# ContunityTestingRig.net
KiCad netlist of a schematic drawn in EAGLE
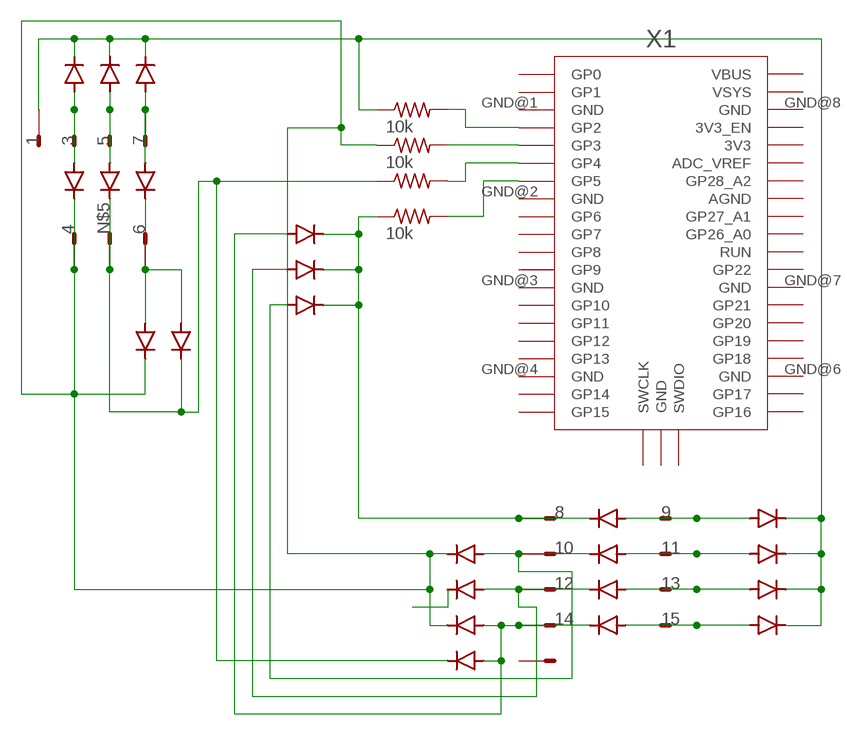
[diagram p0: schematic, sheet 1]

(export (version "E")
  (design (tool "Eeschema 10.0.6"))
  (components
    (comp (ref "D1")
      (value "SCHOTTKY")
      (footprint "eagle-import:MINI-SMA")
      (libsource (lib "eagle-import") (part "DIODE_SCHOTTKY_CDBM1100-G"))
    )
    (comp (ref "D2")
      (value "SCHOTTKY")
      (footprint "eagle-import:MINI-SMA")
      (libsource (lib "eagle-import") (part "DIODE_SCHOTTKY_CDBM1100-G"))
    )
    (comp (ref "D3")
      (value "SCHOTTKY")
      (footprint "eagle-import:MINI-SMA")
      (libsource (lib "eagle-import") (part "DIODE_SCHOTTKY_CDBM1100-G"))
    )
    (comp (ref "D4")
      (value "SCHOTTKY")
      (footprint "eagle-import:MINI-SMA")
      (libsource (lib "eagle-import") (part "DIODE_SCHOTTKY_CDBM1100-G"))
    )
    (comp (ref "D5")
      (value "SCHOTTKY")
      (footprint "eagle-import:MINI-SMA")
      (libsource (lib "eagle-import") (part "DIODE_SCHOTTKY_CDBM1100-G"))
    )
    (comp (ref "D6")
      (value "SCHOTTKY")
      (footprint "eagle-import:MINI-SMA")
      (libsource (lib "eagle-import") (part "DIODE_SCHOTTKY_CDBM1100-G"))
    )
    (comp (ref "D7")
      (value "SCHOTTKY")
      (footprint "eagle-import:MINI-SMA")
      (libsource (lib "eagle-import") (part "DIODE_SCHOTTKY_CDBM1100-G"))
    )
    (comp (ref "D8")
      (value "SCHOTTKY")
      (footprint "eagle-import:MINI-SMA")
      (libsource (lib "eagle-import") (part "DIODE_SCHOTTKY_CDBM1100-G"))
    )
    (comp (ref "D9")
      (value "SCHOTTKY")
      (footprint "eagle-import:MINI-SMA")
      (libsource (lib "eagle-import") (part "DIODE_SCHOTTKY_CDBM1100-G"))
    )
    (comp (ref "D10")
      (value "SCHOTTKY")
      (footprint "eagle-import:MINI-SMA")
      (libsource (lib "eagle-import") (part "DIODE_SCHOTTKY_CDBM1100-G"))
    )
    (comp (ref "D11")
      (value "SCHOTTKY")
      (footprint "eagle-import:MINI-SMA")
      (libsource (lib "eagle-import") (part "DIODE_SCHOTTKY_CDBM1100-G"))
    )
    (comp (ref "D12")
      (value "SCHOTTKY")
      (footprint "eagle-import:MINI-SMA")
      (libsource (lib "eagle-import") (part "DIODE_SCHOTTKY_CDBM1100-G"))
    )
    (comp (ref "D13")
      (value "SCHOTTKY")
      (footprint "eagle-import:MINI-SMA")
      (libsource (lib "eagle-import") (part "DIODE_SCHOTTKY_CDBM1100-G"))
    )
    (comp (ref "D14")
      (value "SCHOTTKY")
      (footprint "eagle-import:MINI-SMA")
      (libsource (lib "eagle-import") (part "DIODE_SCHOTTKY_CDBM1100-G"))
    )
    (comp (ref "D15")
      (value "SCHOTTKY")
      (footprint "eagle-import:MINI-SMA")
      (libsource (lib "eagle-import") (part "DIODE_SCHOTTKY_CDBM1100-G"))
    )
    (comp (ref "D16")
      (value "SCHOTTKY")
      (footprint "eagle-import:MINI-SMA")
      (libsource (lib "eagle-import") (part "DIODE_SCHOTTKY_CDBM1100-G"))
    )
    (comp (ref "D17")
      (value "SCHOTTKY")
      (footprint "eagle-import:MINI-SMA")
      (libsource (lib "eagle-import") (part "DIODE_SCHOTTKY_CDBM1100-G"))
    )
    (comp (ref "D18")
      (value "SCHOTTKY")
      (footprint "eagle-import:MINI-SMA")
      (libsource (lib "eagle-import") (part "DIODE_SCHOTTKY_CDBM1100-G"))
    )
    (comp (ref "D19")
      (value "SCHOTTKY")
      (footprint "eagle-import:MINI-SMA")
      (libsource (lib "eagle-import") (part "DIODE_SCHOTTKY_CDBM1100-G"))
    )
    (comp (ref "D20")
      (value "SCHOTTKY")
      (footprint "eagle-import:MINI-SMA")
      (libsource (lib "eagle-import") (part "DIODE_SCHOTTKY_CDBM1100-G"))
    )
    (comp (ref "D21")
      (value "SCHOTTKY")
      (footprint "eagle-import:MINI-SMA")
      (libsource (lib "eagle-import") (part "DIODE_SCHOTTKY_CDBM1100-G"))
    )
    (comp (ref "D22")
      (value "SCHOTTKY")
      (footprint "eagle-import:MINI-SMA")
      (libsource (lib "eagle-import") (part "DIODE_SCHOTTKY_CDBM1100-G"))
    )
    (comp (ref "D23")
      (value "SCHOTTKY")
      (footprint "eagle-import:MINI-SMA")
      (libsource (lib "eagle-import") (part "DIODE_SCHOTTKY_CDBM1100-G"))
    )
    (comp (ref "R1")
      (value "10k")
      (footprint "eagle-import:R1206FAB")
      (libsource (lib "eagle-import") (part "R1206FAB"))
    )
    (comp (ref "R2")
      (value "10k")
      (footprint "eagle-import:R1206FAB")
      (libsource (lib "eagle-import") (part "R1206FAB"))
    )
    (comp (ref "R3")
      (value "10k")
      (footprint "eagle-import:R1206FAB")
      (libsource (lib "eagle-import") (part "R1206FAB"))
    )
    (comp (ref "R4")
      (value "10k")
      (footprint "eagle-import:R1206FAB")
      (libsource (lib "eagle-import") (part "R1206FAB"))
    )
    (comp (ref "SV1")
      (value "16E")
      (footprint "eagle-import:16P")
      (libsource (lib "eagle-import") (part "16E"))
    )
    (comp (ref "X1")
      (value "RPI_PICO_IG-SMD")
      (footprint "eagle-import:RPI_PICO")
      (libsource (lib "eagle-import") (part "RPI_PICO_IG-SMD"))
    )
  )
  (nets
    (net (code "1") (name "/1") (class "Default")
      (node (ref "D1") (pin "KATHODE") (pinfunction "KATHODE_KATHODE") (pintype "bidirectional"))
      (node (ref "D13") (pin "KATHODE") (pinfunction "KATHODE_KATHODE") (pintype "bidirectional"))
      (node (ref "D14") (pin "KATHODE") (pinfunction "KATHODE_KATHODE") (pintype "bidirectional"))
      (node (ref "D15") (pin "KATHODE") (pinfunction "KATHODE_KATHODE") (pintype "bidirectional"))
      (node (ref "D16") (pin "KATHODE") (pinfunction "KATHODE_KATHODE") (pintype "bidirectional"))
      (node (ref "D2") (pin "KATHODE") (pinfunction "KATHODE_KATHODE") (pintype "bidirectional"))
      (node (ref "D3") (pin "KATHODE") (pinfunction "KATHODE_KATHODE") (pintype "bidirectional"))
      (node (ref "R1") (pin "1") (pinfunction "1_1") (pintype "passive"))
      (node (ref "SV1") (pin "1") (pinfunction "S_1") (pintype "passive"))
    )
    (net (code "2") (name "/3") (class "Default")
      (node (ref "D1") (pin "ANODE") (pinfunction "ANODE_ANODE") (pintype "bidirectional"))
      (node (ref "D4") (pin "ANODE") (pinfunction "ANODE_ANODE") (pintype "bidirectional"))
      (node (ref "SV1") (pin "3") (pinfunction "S_3") (pintype "passive"))
    )
    (net (code "3") (name "/4") (class "Default")
      (node (ref "D17") (pin "KATHODE") (pinfunction "KATHODE_KATHODE") (pintype "bidirectional"))
      (node (ref "D18") (pin "KATHODE") (pinfunction "KATHODE_KATHODE") (pintype "bidirectional"))
      (node (ref "D4") (pin "KATHODE") (pinfunction "KATHODE_KATHODE") (pintype "bidirectional"))
      (node (ref "D7") (pin "KATHODE") (pinfunction "KATHODE_KATHODE") (pintype "bidirectional"))
      (node (ref "R2") (pin "1") (pinfunction "1_1") (pintype "passive"))
      (node (ref "SV1") (pin "2") (pinfunction "S_2") (pintype "passive"))
    )
    (net (code "4") (name "/5") (class "Default")
      (node (ref "D2") (pin "ANODE") (pinfunction "ANODE_ANODE") (pintype "bidirectional"))
      (node (ref "D5") (pin "ANODE") (pinfunction "ANODE_ANODE") (pintype "bidirectional"))
      (node (ref "SV1") (pin "5") (pinfunction "S_5") (pintype "passive"))
    )
    (net (code "5") (name "/6") (class "Default")
      (node (ref "D6") (pin "KATHODE") (pinfunction "KATHODE_KATHODE") (pintype "bidirectional"))
      (node (ref "D7") (pin "ANODE") (pinfunction "ANODE_ANODE") (pintype "bidirectional"))
      (node (ref "D8") (pin "ANODE") (pinfunction "ANODE_ANODE") (pintype "bidirectional"))
      (node (ref "SV1") (pin "6") (pinfunction "S_6") (pintype "passive"))
    )
    (net (code "6") (name "/7") (class "Default")
      (node (ref "D3") (pin "ANODE") (pinfunction "ANODE_ANODE") (pintype "bidirectional"))
      (node (ref "D6") (pin "ANODE") (pinfunction "ANODE_ANODE") (pintype "bidirectional"))
      (node (ref "SV1") (pin "7") (pinfunction "S_7") (pintype "passive"))
    )
    (net (code "7") (name "/8") (class "Default")
      (node (ref "D21") (pin "KATHODE") (pinfunction "KATHODE_KATHODE") (pintype "bidirectional"))
      (node (ref "D22") (pin "KATHODE") (pinfunction "KATHODE_KATHODE") (pintype "bidirectional"))
      (node (ref "D23") (pin "KATHODE") (pinfunction "KATHODE_KATHODE") (pintype "bidirectional"))
      (node (ref "D9") (pin "KATHODE") (pinfunction "KATHODE_KATHODE") (pintype "bidirectional"))
      (node (ref "R4") (pin "1") (pinfunction "1_1") (pintype "passive"))
      (node (ref "SV1") (pin "8") (pinfunction "S_8") (pintype "passive"))
    )
    (net (code "8") (name "/9") (class "Default")
      (node (ref "D13") (pin "ANODE") (pinfunction "ANODE_ANODE") (pintype "bidirectional"))
      (node (ref "D9") (pin "ANODE") (pinfunction "ANODE_ANODE") (pintype "bidirectional"))
      (node (ref "SV1") (pin "9") (pinfunction "S_9") (pintype "passive"))
    )
    (net (code "9") (name "/10") (class "Default")
      (node (ref "D10") (pin "KATHODE") (pinfunction "KATHODE_KATHODE") (pintype "bidirectional"))
      (node (ref "D17") (pin "ANODE") (pinfunction "ANODE_ANODE") (pintype "bidirectional"))
      (node (ref "D23") (pin "ANODE") (pinfunction "ANODE_ANODE") (pintype "bidirectional"))
      (node (ref "SV1") (pin "10") (pinfunction "S_10") (pintype "passive"))
    )
    (net (code "10") (name "/11") (class "Default")
      (node (ref "D10") (pin "ANODE") (pinfunction "ANODE_ANODE") (pintype "bidirectional"))
      (node (ref "D14") (pin "ANODE") (pinfunction "ANODE_ANODE") (pintype "bidirectional"))
      (node (ref "SV1") (pin "11") (pinfunction "S_11") (pintype "passive"))
    )
    (net (code "11") (name "/12") (class "Default")
      (node (ref "D11") (pin "KATHODE") (pinfunction "KATHODE_KATHODE") (pintype "bidirectional"))
      (node (ref "D19") (pin "ANODE") (pinfunction "ANODE_ANODE") (pintype "bidirectional"))
      (node (ref "D22") (pin "ANODE") (pinfunction "ANODE_ANODE") (pintype "bidirectional"))
      (node (ref "SV1") (pin "12") (pinfunction "S_12") (pintype "passive"))
    )
    (net (code "12") (name "/13") (class "Default")
      (node (ref "D11") (pin "ANODE") (pinfunction "ANODE_ANODE") (pintype "bidirectional"))
      (node (ref "D15") (pin "ANODE") (pinfunction "ANODE_ANODE") (pintype "bidirectional"))
      (node (ref "SV1") (pin "13") (pinfunction "S_13") (pintype "passive"))
    )
    (net (code "13") (name "/14") (class "Default")
      (node (ref "D12") (pin "KATHODE") (pinfunction "KATHODE_KATHODE") (pintype "bidirectional"))
      (node (ref "D18") (pin "ANODE") (pinfunction "ANODE_ANODE") (pintype "bidirectional"))
      (node (ref "D20") (pin "ANODE") (pinfunction "ANODE_ANODE") (pintype "bidirectional"))
      (node (ref "D21") (pin "ANODE") (pinfunction "ANODE_ANODE") (pintype "bidirectional"))
      (node (ref "SV1") (pin "14") (pinfunction "S_14") (pintype "passive"))
    )
    (net (code "14") (name "/15") (class "Default")
      (node (ref "D12") (pin "ANODE") (pinfunction "ANODE_ANODE") (pintype "bidirectional"))
      (node (ref "D16") (pin "ANODE") (pinfunction "ANODE_ANODE") (pintype "bidirectional"))
      (node (ref "SV1") (pin "15") (pinfunction "S_15") (pintype "passive"))
    )
    (net (code "15") (name "/N$5") (class "Default")
      (node (ref "D20") (pin "KATHODE") (pinfunction "KATHODE_KATHODE") (pintype "bidirectional"))
      (node (ref "D5") (pin "KATHODE") (pinfunction "KATHODE_KATHODE") (pintype "bidirectional"))
      (node (ref "D8") (pin "KATHODE") (pinfunction "KATHODE_KATHODE") (pintype "bidirectional"))
      (node (ref "R3") (pin "1") (pinfunction "1_1") (pintype "passive"))
      (node (ref "SV1") (pin "4") (pinfunction "S_4") (pintype "passive"))
    )
    (net (code "16") (name "Net-(R1-Pad2)") (class "Default")
      (node (ref "R1") (pin "2") (pinfunction "2_2") (pintype "passive"))
      (node (ref "X1") (pin "GP2") (pinfunction "GP2_GP2") (pintype "bidirectional"))
    )
    (net (code "17") (name "Net-(R2-Pad2)") (class "Default")
      (node (ref "R2") (pin "2") (pinfunction "2_2") (pintype "passive"))
      (node (ref "X1") (pin "GP3") (pinfunction "GP3_GP3") (pintype "bidirectional"))
    )
    (net (code "18") (name "Net-(R3-Pad2)") (class "Default")
      (node (ref "R3") (pin "2") (pinfunction "2_2") (pintype "passive"))
      (node (ref "X1") (pin "GP4") (pinfunction "GP4_GP4") (pintype "bidirectional"))
    )
    (net (code "19") (name "Net-(R4-Pad2)") (class "Default")
      (node (ref "R4") (pin "2") (pinfunction "2_2") (pintype "passive"))
      (node (ref "X1") (pin "GP5") (pinfunction "GP5_GP5") (pintype "bidirectional"))
    )
    (net (code "20") (name "unconnected-(D19-PadKATHODE)") (class "Default")
      (node (ref "D19") (pin "KATHODE") (pinfunction "KATHODE_KATHODE") (pintype "bidirectional"))
    )
    (net (code "21") (name "unconnected-(SV1H-S-Pad16)") (class "Default")
      (node (ref "SV1") (pin "16") (pinfunction "S_16") (pintype "passive"))
    )
    (net (code "22") (name "unconnected-(X1-GND-PadGND@1)") (class "Default")
      (node (ref "X1") (pin "GND@1") (pinfunction "GND_GND@1") (pintype "bidirectional"))
    )
    (net (code "23") (name "unconnected-(X1-GND-PadGND@2)") (class "Default")
      (node (ref "X1") (pin "GND@2") (pinfunction "GND_GND@2") (pintype "bidirectional"))
    )
    (net (code "24") (name "unconnected-(X1-GND-PadGND@3)") (class "Default")
      (node (ref "X1") (pin "GND@3") (pinfunction "GND_GND@3") (pintype "bidirectional"))
    )
    (net (code "25") (name "unconnected-(X1-GND-PadGND@4)") (class "Default")
      (node (ref "X1") (pin "GND@4") (pinfunction "GND_GND@4") (pintype "bidirectional"))
    )
    (net (code "26") (name "unconnected-(X1-GND-PadGND@5)") (class "Default")
      (node (ref "X1") (pin "GND@5") (pinfunction "GND_GND@5") (pintype "bidirectional"))
    )
    (net (code "27") (name "unconnected-(X1-GND-PadGND@6)") (class "Default")
      (node (ref "X1") (pin "GND@6") (pinfunction "GND_GND@6") (pintype "bidirectional"))
    )
    (net (code "28") (name "unconnected-(X1-GND-PadGND@7)") (class "Default")
      (node (ref "X1") (pin "GND@7") (pinfunction "GND_GND@7") (pintype "bidirectional"))
    )
    (net (code "29") (name "unconnected-(X1-GND-PadGND@8)") (class "Default")
      (node (ref "X1") (pin "GND@8") (pinfunction "GND_GND@8") (pintype "bidirectional"))
    )
    (net (code "30") (name "unconnected-(X1-Pad3V3)") (class "Default")
      (node (ref "X1") (pin "3V3") (pinfunction "3V3_3V3") (pintype "bidirectional"))
    )
    (net (code "31") (name "unconnected-(X1-Pad3V3_EN)") (class "Default")
      (node (ref "X1") (pin "3V3_EN") (pinfunction "3V3_EN_3V3_EN") (pintype "bidirectional"))
    )
    (net (code "32") (name "unconnected-(X1-PadADC_VREF)") (class "Default")
      (node (ref "X1") (pin "ADC_VREF") (pinfunction "ADC_VREF_ADC_VREF") (pintype "bidirectional"))
    )
    (net (code "33") (name "unconnected-(X1-PadAGND)") (class "Default")
      (node (ref "X1") (pin "AGND") (pinfunction "AGND_AGND") (pintype "bidirectional"))
    )
    (net (code "34") (name "unconnected-(X1-PadGP0)") (class "Default")
      (node (ref "X1") (pin "GP0") (pinfunction "GP0_GP0") (pintype "bidirectional"))
    )
    (net (code "35") (name "unconnected-(X1-PadGP1)") (class "Default")
      (node (ref "X1") (pin "GP1") (pinfunction "GP1_GP1") (pintype "bidirectional"))
    )
    (net (code "36") (name "unconnected-(X1-PadGP6)") (class "Default")
      (node (ref "X1") (pin "GP6") (pinfunction "GP6_GP6") (pintype "bidirectional"))
    )
    (net (code "37") (name "unconnected-(X1-PadGP7)") (class "Default")
      (node (ref "X1") (pin "GP7") (pinfunction "GP7_GP7") (pintype "bidirectional"))
    )
    (net (code "38") (name "unconnected-(X1-PadGP8)") (class "Default")
      (node (ref "X1") (pin "GP8") (pinfunction "GP8_GP8") (pintype "bidirectional"))
    )
    (net (code "39") (name "unconnected-(X1-PadGP9)") (class "Default")
      (node (ref "X1") (pin "GP9") (pinfunction "GP9_GP9") (pintype "bidirectional"))
    )
    (net (code "40") (name "unconnected-(X1-PadGP10)") (class "Default")
      (node (ref "X1") (pin "GP10") (pinfunction "GP10_GP10") (pintype "bidirectional"))
    )
    (net (code "41") (name "unconnected-(X1-PadGP11)") (class "Default")
      (node (ref "X1") (pin "GP11") (pinfunction "GP11_GP11") (pintype "bidirectional"))
    )
    (net (code "42") (name "unconnected-(X1-PadGP12)") (class "Default")
      (node (ref "X1") (pin "GP12") (pinfunction "GP12_GP12") (pintype "bidirectional"))
    )
    (net (code "43") (name "unconnected-(X1-PadGP13)") (class "Default")
      (node (ref "X1") (pin "GP13") (pinfunction "GP13_GP13") (pintype "bidirectional"))
    )
    (net (code "44") (name "unconnected-(X1-PadGP14)") (class "Default")
      (node (ref "X1") (pin "GP14") (pinfunction "GP14_GP14") (pintype "bidirectional"))
    )
    (net (code "45") (name "unconnected-(X1-PadGP15)") (class "Default")
      (node (ref "X1") (pin "GP15") (pinfunction "GP15_GP15") (pintype "bidirectional"))
    )
    (net (code "46") (name "unconnected-(X1-PadGP16)") (class "Default")
      (node (ref "X1") (pin "GP16") (pinfunction "GP16_GP16") (pintype "bidirectional"))
    )
    (net (code "47") (name "unconnected-(X1-PadGP17)") (class "Default")
      (node (ref "X1") (pin "GP17") (pinfunction "GP17_GP17") (pintype "bidirectional"))
    )
    (net (code "48") (name "unconnected-(X1-PadGP18)") (class "Default")
      (node (ref "X1") (pin "GP18") (pinfunction "GP18_GP18") (pintype "bidirectional"))
    )
    (net (code "49") (name "unconnected-(X1-PadGP19)") (class "Default")
      (node (ref "X1") (pin "GP19") (pinfunction "GP19_GP19") (pintype "bidirectional"))
    )
    (net (code "50") (name "unconnected-(X1-PadGP20)") (class "Default")
      (node (ref "X1") (pin "GP20") (pinfunction "GP20_GP20") (pintype "bidirectional"))
    )
    (net (code "51") (name "unconnected-(X1-PadGP21)") (class "Default")
      (node (ref "X1") (pin "GP21") (pinfunction "GP21_GP21") (pintype "bidirectional"))
    )
    (net (code "52") (name "unconnected-(X1-PadGP22)") (class "Default")
      (node (ref "X1") (pin "GP22") (pinfunction "GP22_GP22") (pintype "bidirectional"))
    )
    (net (code "53") (name "unconnected-(X1-PadGP26_A0)") (class "Default")
      (node (ref "X1") (pin "GP26_A0") (pinfunction "GP26_A0_GP26_A0") (pintype "bidirectional"))
    )
    (net (code "54") (name "unconnected-(X1-PadGP27_A1)") (class "Default")
      (node (ref "X1") (pin "GP27_A1") (pinfunction "GP27_A1_GP27_A1") (pintype "bidirectional"))
    )
    (net (code "55") (name "unconnected-(X1-PadGP28_A2)") (class "Default")
      (node (ref "X1") (pin "GP28_A2") (pinfunction "GP28_A2_GP28_A2") (pintype "bidirectional"))
    )
    (net (code "56") (name "unconnected-(X1-PadRUN)") (class "Default")
      (node (ref "X1") (pin "RUN") (pinfunction "RUN_RUN") (pintype "bidirectional"))
    )
    (net (code "57") (name "unconnected-(X1-PadSWCLK)") (class "Default")
      (node (ref "X1") (pin "SWCLK") (pinfunction "SWCLK_SWCLK") (pintype "bidirectional"))
    )
    (net (code "58") (name "unconnected-(X1-PadSWDIO)") (class "Default")
      (node (ref "X1") (pin "SWDIO") (pinfunction "SWDIO_SWDIO") (pintype "bidirectional"))
    )
    (net (code "59") (name "unconnected-(X1-PadVBUS)") (class "Default")
      (node (ref "X1") (pin "VBUS") (pinfunction "VBUS_VBUS") (pintype "bidirectional"))
    )
    (net (code "60") (name "unconnected-(X1-PadVSYS)") (class "Default")
      (node (ref "X1") (pin "VSYS") (pinfunction "VSYS_VSYS") (pintype "bidirectional"))
    )
  )
)
